# LED_Matrix.net
KiCad netlist of a schematic drawn in Altium Designer
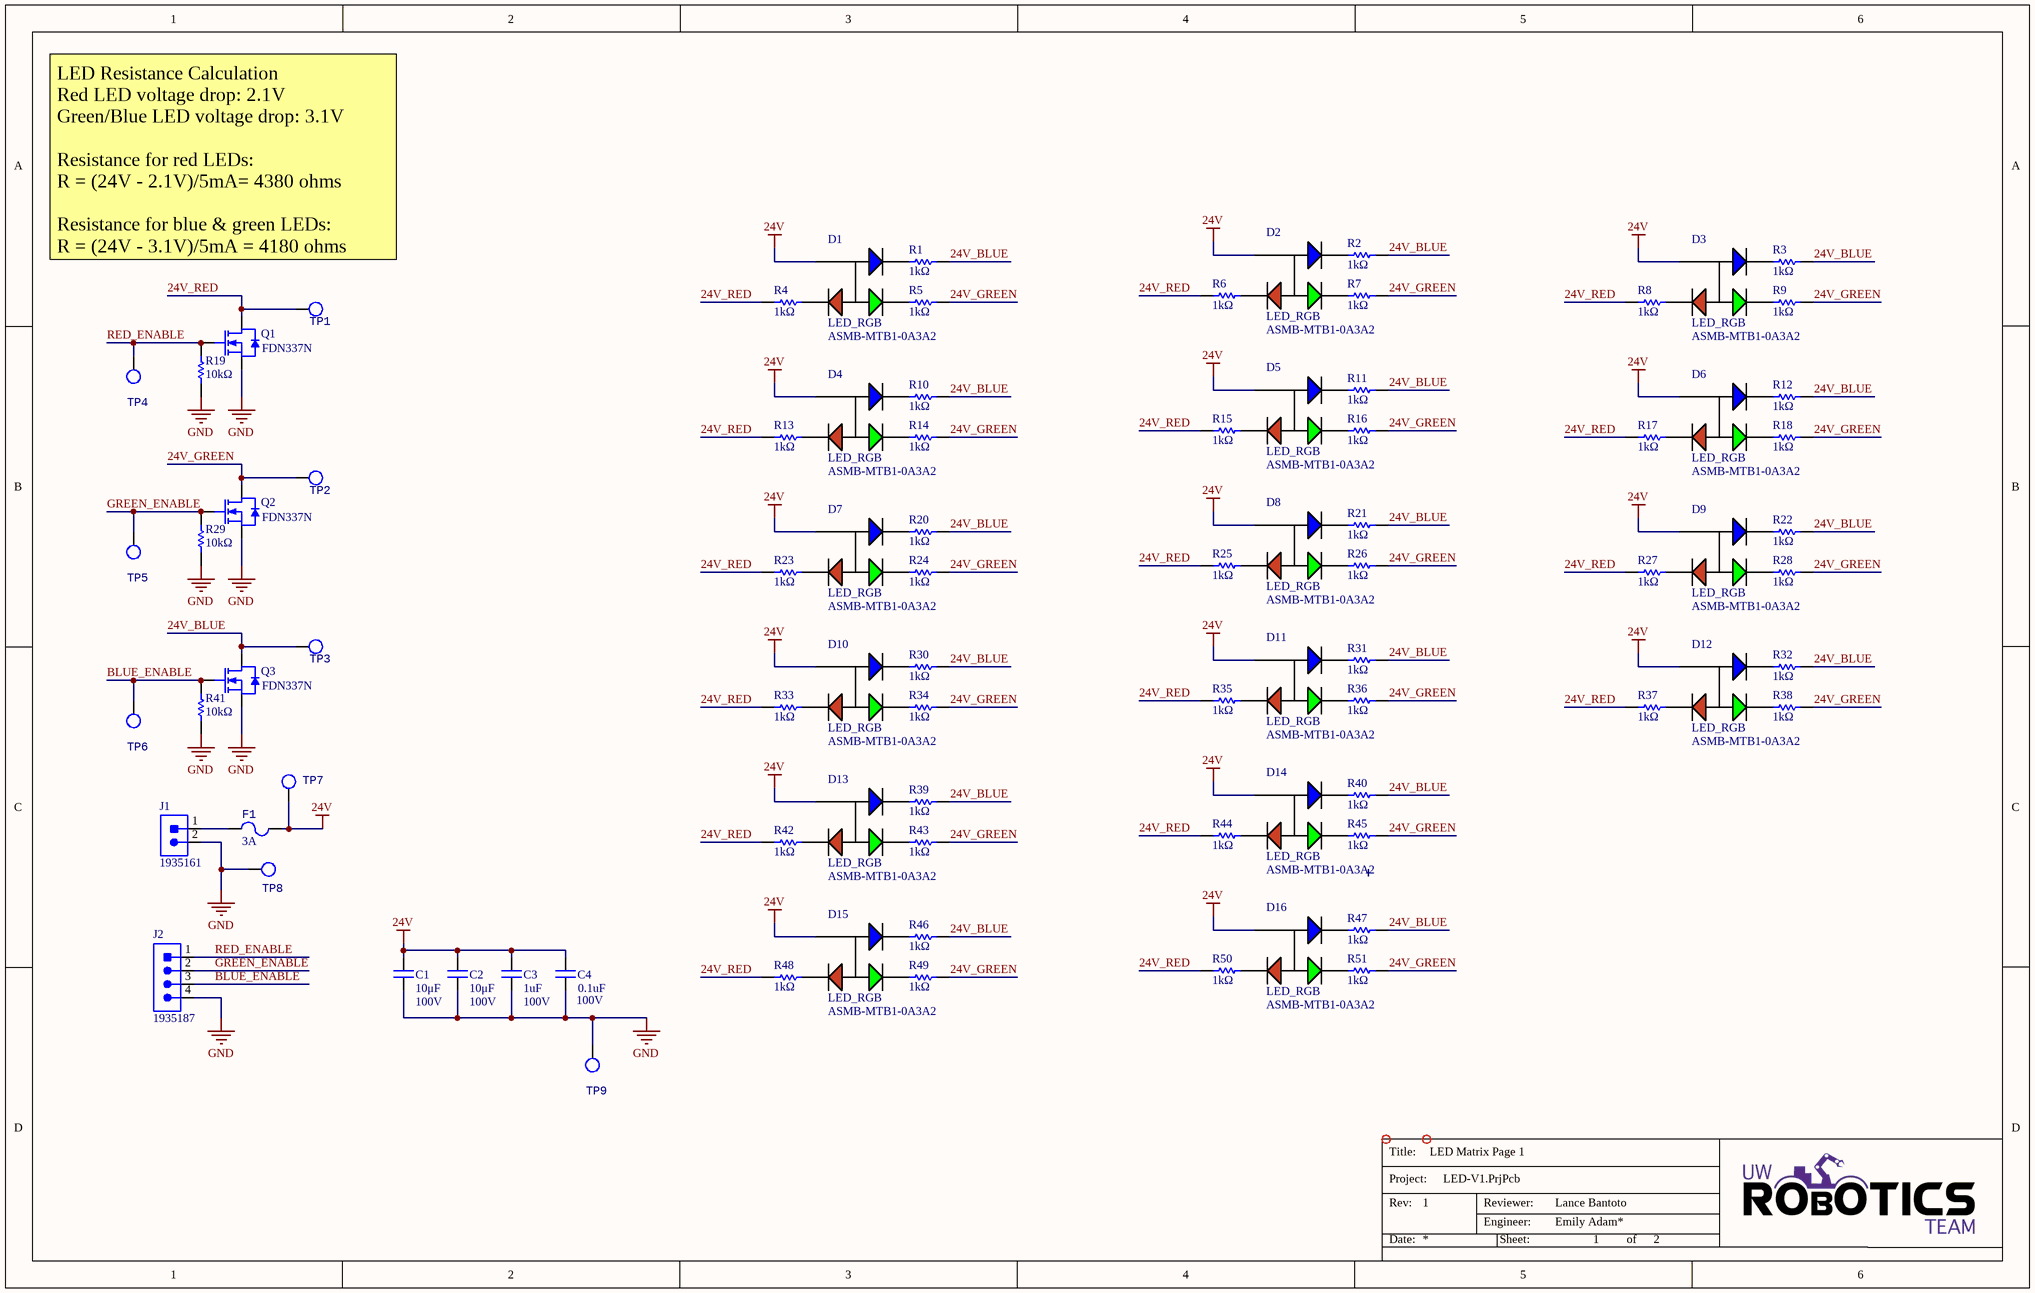
[diagram p0: LED Matrix.SchDoc]

(export (version "E")
  (design (tool "Eeschema 10.0.6"))
  (components
    (comp (ref "C1")
      (value "10μF")
      (footprint "CAP1210")
      (description "CAP CER 10uF 100V X7S 10% 1210")
      (fields
        (field (name "TOLERANCE") "10%")
        (field (name "VOLTAGE RATING") "100V")
        (field (name "Comment") "CAP_10uF_100V_1210")
      )
      (libsource (lib "UWRT_Schematic_Library_2020") (part "CAP_10uF_100V_1210"))
    )
    (comp (ref "C2")
      (value "10μF")
      (footprint "CAP1210")
      (description "CAP CER 10uF 100V X7S 10% 1210")
      (fields
        (field (name "TOLERANCE") "10%")
        (field (name "VOLTAGE RATING") "100V")
        (field (name "Comment") "CAP_10uF_100V_1210")
      )
      (libsource (lib "UWRT_Schematic_Library_2020") (part "CAP_10uF_100V_1210"))
    )
    (comp (ref "C3")
      (value "CAP_1uF_100V_1206")
      (footprint "CAPC3216X190X50NL20T25")
      (description "CAP CER 1UF 100V X7R 1206")
      (fields
        (field (name "MANUFACTURER") "Murata")
        (field (name "MANUFACTURER PART NUMBER") "GCJ31CR72A105KA01L")
        (field (name "CAPACITANCE") "1uF")
        (field (name "VOLTAGE RATING") "100V")
      )
      (libsource (lib "UWRT_Schematic_Library_2020") (part "CAP_1uF_100V_1206"))
    )
    (comp (ref "C4")
      (value "CAP_0.1uF_100V_1206")
      (footprint "CAPC3216X180N")
      (description "CAP CER 0.1UF 100V C0G/NP0 1206")
      (fields
        (field (name "MANUFACTURER") "Murata")
        (field (name "MANUFACTURER PART NUMBER") "GRM31C5C2A104JA01L")
        (field (name "VOLTAGE RATING (DC)") "100V")
        (field (name "CAPACITANCE") "0.1uF")
      )
      (libsource (lib "UWRT_Schematic_Library_2020") (part "CAP_0.1uF_100V_1206"))
    )
    (comp (ref "D1")
      (value "LED_RGB")
      (footprint "LED_RGB")
      (description "LED RGB DIFFUSED 4PLCC SMD")
      (fields (field (name "MANUFACTURER PART NUMBER 1") "ASMB-MTB1-0A3A2"))
      (libsource (lib "UWRT_Schematic_Library_2020") (part "LED_RGB"))
    )
    (comp (ref "D2")
      (value "LED_RGB")
      (footprint "LED_RGB")
      (description "LED RGB DIFFUSED 4PLCC SMD")
      (fields (field (name "MANUFACTURER PART NUMBER 1") "ASMB-MTB1-0A3A2"))
      (libsource (lib "UWRT_Schematic_Library_2020") (part "LED_RGB"))
    )
    (comp (ref "D3")
      (value "LED_RGB")
      (footprint "LED_RGB")
      (description "LED RGB DIFFUSED 4PLCC SMD")
      (fields (field (name "MANUFACTURER PART NUMBER 1") "ASMB-MTB1-0A3A2"))
      (libsource (lib "UWRT_Schematic_Library_2020") (part "LED_RGB"))
    )
    (comp (ref "D4")
      (value "LED_RGB")
      (footprint "LED_RGB")
      (description "LED RGB DIFFUSED 4PLCC SMD")
      (fields (field (name "MANUFACTURER PART NUMBER 1") "ASMB-MTB1-0A3A2"))
      (libsource (lib "UWRT_Schematic_Library_2020") (part "LED_RGB"))
    )
    (comp (ref "D5")
      (value "LED_RGB")
      (footprint "LED_RGB")
      (description "LED RGB DIFFUSED 4PLCC SMD")
      (fields (field (name "MANUFACTURER PART NUMBER 1") "ASMB-MTB1-0A3A2"))
      (libsource (lib "UWRT_Schematic_Library_2020") (part "LED_RGB"))
    )
    (comp (ref "D6")
      (value "LED_RGB")
      (footprint "LED_RGB")
      (description "LED RGB DIFFUSED 4PLCC SMD")
      (fields (field (name "MANUFACTURER PART NUMBER 1") "ASMB-MTB1-0A3A2"))
      (libsource (lib "UWRT_Schematic_Library_2020") (part "LED_RGB"))
    )
    (comp (ref "D7")
      (value "LED_RGB")
      (footprint "LED_RGB")
      (description "LED RGB DIFFUSED 4PLCC SMD")
      (fields (field (name "MANUFACTURER PART NUMBER 1") "ASMB-MTB1-0A3A2"))
      (libsource (lib "UWRT_Schematic_Library_2020") (part "LED_RGB"))
    )
    (comp (ref "D8")
      (value "LED_RGB")
      (footprint "LED_RGB")
      (description "LED RGB DIFFUSED 4PLCC SMD")
      (fields (field (name "MANUFACTURER PART NUMBER 1") "ASMB-MTB1-0A3A2"))
      (libsource (lib "UWRT_Schematic_Library_2020") (part "LED_RGB"))
    )
    (comp (ref "D9")
      (value "LED_RGB")
      (footprint "LED_RGB")
      (description "LED RGB DIFFUSED 4PLCC SMD")
      (fields (field (name "MANUFACTURER PART NUMBER 1") "ASMB-MTB1-0A3A2"))
      (libsource (lib "UWRT_Schematic_Library_2020") (part "LED_RGB"))
    )
    (comp (ref "D10")
      (value "LED_RGB")
      (footprint "LED_RGB")
      (description "LED RGB DIFFUSED 4PLCC SMD")
      (fields (field (name "MANUFACTURER PART NUMBER 1") "ASMB-MTB1-0A3A2"))
      (libsource (lib "UWRT_Schematic_Library_2020") (part "LED_RGB"))
    )
    (comp (ref "D11")
      (value "LED_RGB")
      (footprint "LED_RGB")
      (description "LED RGB DIFFUSED 4PLCC SMD")
      (fields (field (name "MANUFACTURER PART NUMBER 1") "ASMB-MTB1-0A3A2"))
      (libsource (lib "UWRT_Schematic_Library_2020") (part "LED_RGB"))
    )
    (comp (ref "D12")
      (value "LED_RGB")
      (footprint "LED_RGB")
      (description "LED RGB DIFFUSED 4PLCC SMD")
      (fields (field (name "MANUFACTURER PART NUMBER 1") "ASMB-MTB1-0A3A2"))
      (libsource (lib "UWRT_Schematic_Library_2020") (part "LED_RGB"))
    )
    (comp (ref "D13")
      (value "LED_RGB")
      (footprint "LED_RGB")
      (description "LED RGB DIFFUSED 4PLCC SMD")
      (fields (field (name "MANUFACTURER PART NUMBER 1") "ASMB-MTB1-0A3A2"))
      (libsource (lib "UWRT_Schematic_Library_2020") (part "LED_RGB"))
    )
    (comp (ref "D14")
      (value "LED_RGB")
      (footprint "LED_RGB")
      (description "LED RGB DIFFUSED 4PLCC SMD")
      (fields (field (name "MANUFACTURER PART NUMBER 1") "ASMB-MTB1-0A3A2"))
      (libsource (lib "UWRT_Schematic_Library_2020") (part "LED_RGB"))
    )
    (comp (ref "D15")
      (value "LED_RGB")
      (footprint "LED_RGB")
      (description "LED RGB DIFFUSED 4PLCC SMD")
      (fields (field (name "MANUFACTURER PART NUMBER 1") "ASMB-MTB1-0A3A2"))
      (libsource (lib "UWRT_Schematic_Library_2020") (part "LED_RGB"))
    )
    (comp (ref "D16")
      (value "LED_RGB")
      (footprint "LED_RGB")
      (description "LED RGB DIFFUSED 4PLCC SMD")
      (fields (field (name "MANUFACTURER PART NUMBER 1") "ASMB-MTB1-0A3A2"))
      (libsource (lib "UWRT_Schematic_Library_2020") (part "LED_RGB"))
    )
    (comp (ref "F1")
      (value "FUSE_3A_1206")
      (footprint "FUSE_1206")
      (description "FUSE BOARD MNT 3A 32VAC/VDC 1206")
      (fields (field (name "CURRENT RATING") "3A"))
      (libsource (lib "UWRT_Schematic_Library_2020") (part "FUSE_3A_1206"))
    )
    (comp (ref "J1")
      (value "CON_2M_TERM")
      (footprint "1935161")
      (description "TERM BLK 2POS SIDE ENTRY 5MM")
      (fields (field (name "VOLTAGE") "300V") (field (name "MANUFACTURER PART NUMBER 1") "1935161"))
      (libsource (lib "UWRT_Schematic_Library_2020") (part "CON_2M_TERM"))
    )
    (comp (ref "J2")
      (value "CON_4M_TERM")
      (footprint "1935187")
      (description "TERM BLK 4POS SIDE ENTRY 5MM PCB")
      (fields (field (name "VOLTAGE") "300V") (field (name "MANUFACTURER PART NUMBER 1") "1935187"))
      (libsource (lib "UWRT_Schematic_Library_2020") (part "CON_4M_TERM"))
    )
    (comp (ref "MH1")
      (value "MOUNTING_HOLES")
      (footprint "MOUNTING_HOLE")
      (description "6cm x 6cm")
      (libsource (lib "UWRT_Schematic_Library_2020") (part "MOUNTING_HOLES"))
    )
    (comp (ref "MH2")
      (value "MOUNTING_HOLES")
      (footprint "MOUNTING_HOLE")
      (description "6cm x 6cm")
      (libsource (lib "UWRT_Schematic_Library_2020") (part "MOUNTING_HOLES"))
    )
    (comp (ref "Q1")
      (value "NMOS_30V_2.2A")
      (footprint "NMOS_SSOT-3")
      (description "MOSFET N-CH 30V 2.2A SUPERSOT3")
      (fields (field (name "MANUFACTURER PART NUMBER 1") "FDN337N"))
      (libsource (lib "UWRT_Schematic_Library_2020") (part "NMOS_30V_2.2A"))
    )
    (comp (ref "Q2")
      (value "NMOS_30V_2.2A")
      (footprint "NMOS_SSOT-3")
      (description "MOSFET N-CH 30V 2.2A SUPERSOT3")
      (fields (field (name "MANUFACTURER PART NUMBER 1") "FDN337N"))
      (libsource (lib "UWRT_Schematic_Library_2020") (part "NMOS_30V_2.2A"))
    )
    (comp (ref "Q3")
      (value "NMOS_30V_2.2A")
      (footprint "NMOS_SSOT-3")
      (description "MOSFET N-CH 30V 2.2A SUPERSOT3")
      (fields (field (name "MANUFACTURER PART NUMBER 1") "FDN337N"))
      (libsource (lib "UWRT_Schematic_Library_2020") (part "NMOS_30V_2.2A"))
    )
    (comp (ref "R1")
      (value "1kΩ")
      (footprint "RESC2012X60N")
      (description "RES SMD 1K OHM 1% 1/8W 0805")
      (fields (field (name "TOLERANCE") "1%"))
      (libsource (lib "UWRT_Schematic_Library_2020") (part "RES_1kΩ_0805"))
    )
    (comp (ref "R2")
      (value "1kΩ")
      (footprint "RESC2012X60N")
      (description "RES SMD 1K OHM 1% 1/8W 0805")
      (fields (field (name "TOLERANCE") "1%"))
      (libsource (lib "UWRT_Schematic_Library_2020") (part "RES_1kΩ_0805"))
    )
    (comp (ref "R3")
      (value "1kΩ")
      (footprint "RESC2012X60N")
      (description "RES SMD 1K OHM 1% 1/8W 0805")
      (fields (field (name "TOLERANCE") "1%"))
      (libsource (lib "UWRT_Schematic_Library_2020") (part "RES_1kΩ_0805"))
    )
    (comp (ref "R4")
      (value "1kΩ")
      (footprint "RESC2012X60N")
      (description "RES SMD 1K OHM 1% 1/8W 0805")
      (fields (field (name "TOLERANCE") "1%"))
      (libsource (lib "UWRT_Schematic_Library_2020") (part "RES_1kΩ_0805"))
    )
    (comp (ref "R5")
      (value "1kΩ")
      (footprint "RESC2012X60N")
      (description "RES SMD 1K OHM 1% 1/8W 0805")
      (fields (field (name "TOLERANCE") "1%"))
      (libsource (lib "UWRT_Schematic_Library_2020") (part "RES_1kΩ_0805"))
    )
    (comp (ref "R6")
      (value "1kΩ")
      (footprint "RESC2012X60N")
      (description "RES SMD 1K OHM 1% 1/8W 0805")
      (fields (field (name "TOLERANCE") "1%"))
      (libsource (lib "UWRT_Schematic_Library_2020") (part "RES_1kΩ_0805"))
    )
    (comp (ref "R7")
      (value "1kΩ")
      (footprint "RESC2012X60N")
      (description "RES SMD 1K OHM 1% 1/8W 0805")
      (fields (field (name "TOLERANCE") "1%"))
      (libsource (lib "UWRT_Schematic_Library_2020") (part "RES_1kΩ_0805"))
    )
    (comp (ref "R8")
      (value "1kΩ")
      (footprint "RESC2012X60N")
      (description "RES SMD 1K OHM 1% 1/8W 0805")
      (fields (field (name "TOLERANCE") "1%"))
      (libsource (lib "UWRT_Schematic_Library_2020") (part "RES_1kΩ_0805"))
    )
    (comp (ref "R9")
      (value "1kΩ")
      (footprint "RESC2012X60N")
      (description "RES SMD 1K OHM 1% 1/8W 0805")
      (fields (field (name "TOLERANCE") "1%"))
      (libsource (lib "UWRT_Schematic_Library_2020") (part "RES_1kΩ_0805"))
    )
    (comp (ref "R10")
      (value "1kΩ")
      (footprint "RESC2012X60N")
      (description "RES SMD 1K OHM 1% 1/8W 0805")
      (fields (field (name "TOLERANCE") "1%"))
      (libsource (lib "UWRT_Schematic_Library_2020") (part "RES_1kΩ_0805"))
    )
    (comp (ref "R11")
      (value "1kΩ")
      (footprint "RESC2012X60N")
      (description "RES SMD 1K OHM 1% 1/8W 0805")
      (fields (field (name "TOLERANCE") "1%"))
      (libsource (lib "UWRT_Schematic_Library_2020") (part "RES_1kΩ_0805"))
    )
    (comp (ref "R12")
      (value "1kΩ")
      (footprint "RESC2012X60N")
      (description "RES SMD 1K OHM 1% 1/8W 0805")
      (fields (field (name "TOLERANCE") "1%"))
      (libsource (lib "UWRT_Schematic_Library_2020") (part "RES_1kΩ_0805"))
    )
    (comp (ref "R13")
      (value "1kΩ")
      (footprint "RESC2012X60N")
      (description "RES SMD 1K OHM 1% 1/8W 0805")
      (fields (field (name "TOLERANCE") "1%"))
      (libsource (lib "UWRT_Schematic_Library_2020") (part "RES_1kΩ_0805"))
    )
    (comp (ref "R14")
      (value "1kΩ")
      (footprint "RESC2012X60N")
      (description "RES SMD 1K OHM 1% 1/8W 0805")
      (fields (field (name "TOLERANCE") "1%"))
      (libsource (lib "UWRT_Schematic_Library_2020") (part "RES_1kΩ_0805"))
    )
    (comp (ref "R15")
      (value "1kΩ")
      (footprint "RESC2012X60N")
      (description "RES SMD 1K OHM 1% 1/8W 0805")
      (fields (field (name "TOLERANCE") "1%"))
      (libsource (lib "UWRT_Schematic_Library_2020") (part "RES_1kΩ_0805"))
    )
    (comp (ref "R16")
      (value "1kΩ")
      (footprint "RESC2012X60N")
      (description "RES SMD 1K OHM 1% 1/8W 0805")
      (fields (field (name "TOLERANCE") "1%"))
      (libsource (lib "UWRT_Schematic_Library_2020") (part "RES_1kΩ_0805"))
    )
    (comp (ref "R17")
      (value "1kΩ")
      (footprint "RESC2012X60N")
      (description "RES SMD 1K OHM 1% 1/8W 0805")
      (fields (field (name "TOLERANCE") "1%"))
      (libsource (lib "UWRT_Schematic_Library_2020") (part "RES_1kΩ_0805"))
    )
    (comp (ref "R18")
      (value "1kΩ")
      (footprint "RESC2012X60N")
      (description "RES SMD 1K OHM 1% 1/8W 0805")
      (fields (field (name "TOLERANCE") "1%"))
      (libsource (lib "UWRT_Schematic_Library_2020") (part "RES_1kΩ_0805"))
    )
    (comp (ref "R19")
      (value "10kΩ")
      (footprint "RESC2012X60N")
      (description "RES SMD 10K OHM 1% 1/8W 0805")
      (fields (field (name "TOLERANCE") "1%") (field (name "Comment") "RES_10kΩ_0805"))
      (libsource (lib "UWRT_Schematic_Library_2020") (part "RES_10kΩ_0805"))
    )
    (comp (ref "R20")
      (value "1kΩ")
      (footprint "RESC2012X60N")
      (description "RES SMD 1K OHM 1% 1/8W 0805")
      (fields (field (name "TOLERANCE") "1%"))
      (libsource (lib "UWRT_Schematic_Library_2020") (part "RES_1kΩ_0805"))
    )
    (comp (ref "R21")
      (value "1kΩ")
      (footprint "RESC2012X60N")
      (description "RES SMD 1K OHM 1% 1/8W 0805")
      (fields (field (name "TOLERANCE") "1%"))
      (libsource (lib "UWRT_Schematic_Library_2020") (part "RES_1kΩ_0805"))
    )
    (comp (ref "R22")
      (value "1kΩ")
      (footprint "RESC2012X60N")
      (description "RES SMD 1K OHM 1% 1/8W 0805")
      (fields (field (name "TOLERANCE") "1%"))
      (libsource (lib "UWRT_Schematic_Library_2020") (part "RES_1kΩ_0805"))
    )
    (comp (ref "R23")
      (value "1kΩ")
      (footprint "RESC2012X60N")
      (description "RES SMD 1K OHM 1% 1/8W 0805")
      (fields (field (name "TOLERANCE") "1%"))
      (libsource (lib "UWRT_Schematic_Library_2020") (part "RES_1kΩ_0805"))
    )
    (comp (ref "R24")
      (value "1kΩ")
      (footprint "RESC2012X60N")
      (description "RES SMD 1K OHM 1% 1/8W 0805")
      (fields (field (name "TOLERANCE") "1%"))
      (libsource (lib "UWRT_Schematic_Library_2020") (part "RES_1kΩ_0805"))
    )
    (comp (ref "R25")
      (value "1kΩ")
      (footprint "RESC2012X60N")
      (description "RES SMD 1K OHM 1% 1/8W 0805")
      (fields (field (name "TOLERANCE") "1%"))
      (libsource (lib "UWRT_Schematic_Library_2020") (part "RES_1kΩ_0805"))
    )
    (comp (ref "R26")
      (value "1kΩ")
      (footprint "RESC2012X60N")
      (description "RES SMD 1K OHM 1% 1/8W 0805")
      (fields (field (name "TOLERANCE") "1%"))
      (libsource (lib "UWRT_Schematic_Library_2020") (part "RES_1kΩ_0805"))
    )
    (comp (ref "R27")
      (value "1kΩ")
      (footprint "RESC2012X60N")
      (description "RES SMD 1K OHM 1% 1/8W 0805")
      (fields (field (name "TOLERANCE") "1%"))
      (libsource (lib "UWRT_Schematic_Library_2020") (part "RES_1kΩ_0805"))
    )
    (comp (ref "R28")
      (value "1kΩ")
      (footprint "RESC2012X60N")
      (description "RES SMD 1K OHM 1% 1/8W 0805")
      (fields (field (name "TOLERANCE") "1%"))
      (libsource (lib "UWRT_Schematic_Library_2020") (part "RES_1kΩ_0805"))
    )
    (comp (ref "R29")
      (value "10kΩ")
      (footprint "RESC2012X60N")
      (description "RES SMD 10K OHM 1% 1/8W 0805")
      (fields (field (name "TOLERANCE") "1%") (field (name "Comment") "RES_10kΩ_0805"))
      (libsource (lib "UWRT_Schematic_Library_2020") (part "RES_10kΩ_0805"))
    )
    (comp (ref "R30")
      (value "1kΩ")
      (footprint "RESC2012X60N")
      (description "RES SMD 1K OHM 1% 1/8W 0805")
      (fields (field (name "TOLERANCE") "1%"))
      (libsource (lib "UWRT_Schematic_Library_2020") (part "RES_1kΩ_0805"))
    )
    (comp (ref "R31")
      (value "1kΩ")
      (footprint "RESC2012X60N")
      (description "RES SMD 1K OHM 1% 1/8W 0805")
      (fields (field (name "TOLERANCE") "1%"))
      (libsource (lib "UWRT_Schematic_Library_2020") (part "RES_1kΩ_0805"))
    )
    (comp (ref "R32")
      (value "1kΩ")
      (footprint "RESC2012X60N")
      (description "RES SMD 1K OHM 1% 1/8W 0805")
      (fields (field (name "TOLERANCE") "1%"))
      (libsource (lib "UWRT_Schematic_Library_2020") (part "RES_1kΩ_0805"))
    )
    (comp (ref "R33")
      (value "1kΩ")
      (footprint "RESC2012X60N")
      (description "RES SMD 1K OHM 1% 1/8W 0805")
      (fields (field (name "TOLERANCE") "1%"))
      (libsource (lib "UWRT_Schematic_Library_2020") (part "RES_1kΩ_0805"))
    )
    (comp (ref "R34")
      (value "1kΩ")
      (footprint "RESC2012X60N")
      (description "RES SMD 1K OHM 1% 1/8W 0805")
      (fields (field (name "TOLERANCE") "1%"))
      (libsource (lib "UWRT_Schematic_Library_2020") (part "RES_1kΩ_0805"))
    )
    (comp (ref "R35")
      (value "1kΩ")
      (footprint "RESC2012X60N")
      (description "RES SMD 1K OHM 1% 1/8W 0805")
      (fields (field (name "TOLERANCE") "1%"))
      (libsource (lib "UWRT_Schematic_Library_2020") (part "RES_1kΩ_0805"))
    )
    (comp (ref "R36")
      (value "1kΩ")
      (footprint "RESC2012X60N")
      (description "RES SMD 1K OHM 1% 1/8W 0805")
      (fields (field (name "TOLERANCE") "1%"))
      (libsource (lib "UWRT_Schematic_Library_2020") (part "RES_1kΩ_0805"))
    )
    (comp (ref "R37")
      (value "1kΩ")
      (footprint "RESC2012X60N")
      (description "RES SMD 1K OHM 1% 1/8W 0805")
      (fields (field (name "TOLERANCE") "1%"))
      (libsource (lib "UWRT_Schematic_Library_2020") (part "RES_1kΩ_0805"))
    )
    (comp (ref "R38")
      (value "1kΩ")
      (footprint "RESC2012X60N")
      (description "RES SMD 1K OHM 1% 1/8W 0805")
      (fields (field (name "TOLERANCE") "1%"))
      (libsource (lib "UWRT_Schematic_Library_2020") (part "RES_1kΩ_0805"))
    )
    (comp (ref "R39")
      (value "1kΩ")
      (footprint "RESC2012X60N")
      (description "RES SMD 1K OHM 1% 1/8W 0805")
      (fields (field (name "TOLERANCE") "1%"))
      (libsource (lib "UWRT_Schematic_Library_2020") (part "RES_1kΩ_0805"))
    )
    (comp (ref "R40")
      (value "1kΩ")
      (footprint "RESC2012X60N")
      (description "RES SMD 1K OHM 1% 1/8W 0805")
      (fields (field (name "TOLERANCE") "1%"))
      (libsource (lib "UWRT_Schematic_Library_2020") (part "RES_1kΩ_0805"))
    )
    (comp (ref "R41")
      (value "10kΩ")
      (footprint "RESC2012X60N")
      (description "RES SMD 10K OHM 1% 1/8W 0805")
      (fields (field (name "TOLERANCE") "1%") (field (name "Comment") "RES_10kΩ_0805"))
      (libsource (lib "UWRT_Schematic_Library_2020") (part "RES_10kΩ_0805"))
    )
    (comp (ref "R42")
      (value "1kΩ")
      (footprint "RESC2012X60N")
      (description "RES SMD 1K OHM 1% 1/8W 0805")
      (fields (field (name "TOLERANCE") "1%"))
      (libsource (lib "UWRT_Schematic_Library_2020") (part "RES_1kΩ_0805"))
    )
    (comp (ref "R43")
      (value "1kΩ")
      (footprint "RESC2012X60N")
      (description "RES SMD 1K OHM 1% 1/8W 0805")
      (fields (field (name "TOLERANCE") "1%"))
      (libsource (lib "UWRT_Schematic_Library_2020") (part "RES_1kΩ_0805"))
    )
    (comp (ref "R44")
      (value "1kΩ")
      (footprint "RESC2012X60N")
      (description "RES SMD 1K OHM 1% 1/8W 0805")
      (fields (field (name "TOLERANCE") "1%"))
      (libsource (lib "UWRT_Schematic_Library_2020") (part "RES_1kΩ_0805"))
    )
    (comp (ref "R45")
      (value "1kΩ")
      (footprint "RESC2012X60N")
      (description "RES SMD 1K OHM 1% 1/8W 0805")
      (fields (field (name "TOLERANCE") "1%"))
      (libsource (lib "UWRT_Schematic_Library_2020") (part "RES_1kΩ_0805"))
    )
    (comp (ref "R46")
      (value "1kΩ")
      (footprint "RESC2012X60N")
      (description "RES SMD 1K OHM 1% 1/8W 0805")
      (fields (field (name "TOLERANCE") "1%"))
      (libsource (lib "UWRT_Schematic_Library_2020") (part "RES_1kΩ_0805"))
    )
    (comp (ref "R47")
      (value "1kΩ")
      (footprint "RESC2012X60N")
      (description "RES SMD 1K OHM 1% 1/8W 0805")
      (fields (field (name "TOLERANCE") "1%"))
      (libsource (lib "UWRT_Schematic_Library_2020") (part "RES_1kΩ_0805"))
    )
    (comp (ref "R48")
      (value "1kΩ")
      (footprint "RESC2012X60N")
      (description "RES SMD 1K OHM 1% 1/8W 0805")
      (fields (field (name "TOLERANCE") "1%"))
      (libsource (lib "UWRT_Schematic_Library_2020") (part "RES_1kΩ_0805"))
    )
    (comp (ref "R49")
      (value "1kΩ")
      (footprint "RESC2012X60N")
      (description "RES SMD 1K OHM 1% 1/8W 0805")
      (fields (field (name "TOLERANCE") "1%"))
      (libsource (lib "UWRT_Schematic_Library_2020") (part "RES_1kΩ_0805"))
    )
    (comp (ref "R50")
      (value "1kΩ")
      (footprint "RESC2012X60N")
      (description "RES SMD 1K OHM 1% 1/8W 0805")
      (fields (field (name "TOLERANCE") "1%"))
      (libsource (lib "UWRT_Schematic_Library_2020") (part "RES_1kΩ_0805"))
    )
    (comp (ref "R51")
      (value "1kΩ")
      (footprint "RESC2012X60N")
      (description "RES SMD 1K OHM 1% 1/8W 0805")
      (fields (field (name "TOLERANCE") "1%"))
      (libsource (lib "UWRT_Schematic_Library_2020") (part "RES_1kΩ_0805"))
    )
    (comp (ref "TP1")
      (value "TESTPOINT_LOOP")
      (footprint "TESTPOINT_LOOP")
      (description "PC TEST POINT MINIATURE WHITE")
      (libsource (lib "UWRT_Schematic_Library_2020") (part "TESTPOINT_LOOP"))
    )
    (comp (ref "TP2")
      (value "TESTPOINT_LOOP")
      (footprint "TESTPOINT_LOOP")
      (description "PC TEST POINT MINIATURE WHITE")
      (libsource (lib "UWRT_Schematic_Library_2020") (part "TESTPOINT_LOOP"))
    )
    (comp (ref "TP3")
      (value "TESTPOINT_LOOP")
      (footprint "TESTPOINT_LOOP")
      (description "PC TEST POINT MINIATURE WHITE")
      (libsource (lib "UWRT_Schematic_Library_2020") (part "TESTPOINT_LOOP"))
    )
    (comp (ref "TP4")
      (value "TESTPOINT_LOOP")
      (footprint "TESTPOINT_LOOP")
      (description "PC TEST POINT MINIATURE WHITE")
      (libsource (lib "UWRT_Schematic_Library_2020") (part "TESTPOINT_LOOP"))
    )
    (comp (ref "TP5")
      (value "TESTPOINT_LOOP")
      (footprint "TESTPOINT_LOOP")
      (description "PC TEST POINT MINIATURE WHITE")
      (libsource (lib "UWRT_Schematic_Library_2020") (part "TESTPOINT_LOOP"))
    )
    (comp (ref "TP6")
      (value "TESTPOINT_LOOP")
      (footprint "TESTPOINT_LOOP")
      (description "PC TEST POINT MINIATURE WHITE")
      (libsource (lib "UWRT_Schematic_Library_2020") (part "TESTPOINT_LOOP"))
    )
    (comp (ref "TP7")
      (value "TESTPOINT_LOOP")
      (footprint "TESTPOINT_LOOP")
      (description "PC TEST POINT MINIATURE WHITE")
      (libsource (lib "UWRT_Schematic_Library_2020") (part "TESTPOINT_LOOP"))
    )
    (comp (ref "TP8")
      (value "TESTPOINT_LOOP")
      (footprint "TESTPOINT_LOOP")
      (description "PC TEST POINT MINIATURE WHITE")
      (libsource (lib "UWRT_Schematic_Library_2020") (part "TESTPOINT_LOOP"))
    )
    (comp (ref "TP9")
      (value "TESTPOINT_LOOP")
      (footprint "TESTPOINT_LOOP")
      (description "PC TEST POINT MINIATURE WHITE")
      (libsource (lib "UWRT_Schematic_Library_2020") (part "TESTPOINT_LOOP"))
    )
  )
  (nets
    (net (code "1") (name "/24V_BLUE") (class "Default")
      (node (ref "Q3") (pin "3") (pinfunction "DRAIN_3") (pintype "passive"))
      (node (ref "R1") (pin "2") (pinfunction "2_2") (pintype "passive"))
      (node (ref "R10") (pin "2") (pinfunction "2_2") (pintype "passive"))
      (node (ref "R11") (pin "2") (pinfunction "2_2") (pintype "passive"))
      (node (ref "R12") (pin "2") (pinfunction "2_2") (pintype "passive"))
      (node (ref "R2") (pin "2") (pinfunction "2_2") (pintype "passive"))
      (node (ref "R20") (pin "1") (pinfunction "1_1") (pintype "passive"))
      (node (ref "R21") (pin "1") (pinfunction "1_1") (pintype "passive"))
      (node (ref "R22") (pin "1") (pinfunction "1_1") (pintype "passive"))
      (node (ref "R3") (pin "2") (pinfunction "2_2") (pintype "passive"))
      (node (ref "R30") (pin "2") (pinfunction "2_2") (pintype "passive"))
      (node (ref "R31") (pin "2") (pinfunction "2_2") (pintype "passive"))
      (node (ref "R32") (pin "2") (pinfunction "2_2") (pintype "passive"))
      (node (ref "R39") (pin "1") (pinfunction "1_1") (pintype "passive"))
      (node (ref "R40") (pin "2") (pinfunction "2_2") (pintype "passive"))
      (node (ref "R46") (pin "2") (pinfunction "2_2") (pintype "passive"))
      (node (ref "R47") (pin "2") (pinfunction "2_2") (pintype "passive"))
      (node (ref "TP3") (pin "1") (pintype "passive"))
    )
    (net (code "2") (name "/24V_GREEN") (class "Default")
      (node (ref "Q2") (pin "3") (pinfunction "DRAIN_3") (pintype "passive"))
      (node (ref "R14") (pin "2") (pinfunction "2_2") (pintype "passive"))
      (node (ref "R16") (pin "2") (pinfunction "2_2") (pintype "passive"))
      (node (ref "R18") (pin "2") (pinfunction "2_2") (pintype "passive"))
      (node (ref "R24") (pin "2") (pinfunction "2_2") (pintype "passive"))
      (node (ref "R26") (pin "2") (pinfunction "2_2") (pintype "passive"))
      (node (ref "R28") (pin "2") (pinfunction "2_2") (pintype "passive"))
      (node (ref "R34") (pin "2") (pinfunction "2_2") (pintype "passive"))
      (node (ref "R36") (pin "2") (pinfunction "2_2") (pintype "passive"))
      (node (ref "R38") (pin "2") (pinfunction "2_2") (pintype "passive"))
      (node (ref "R43") (pin "2") (pinfunction "2_2") (pintype "passive"))
      (node (ref "R45") (pin "2") (pinfunction "2_2") (pintype "passive"))
      (node (ref "R49") (pin "2") (pinfunction "2_2") (pintype "passive"))
      (node (ref "R5") (pin "2") (pinfunction "2_2") (pintype "passive"))
      (node (ref "R51") (pin "2") (pinfunction "2_2") (pintype "passive"))
      (node (ref "R7") (pin "2") (pinfunction "2_2") (pintype "passive"))
      (node (ref "R9") (pin "2") (pinfunction "2_2") (pintype "passive"))
      (node (ref "TP2") (pin "1") (pintype "passive"))
    )
    (net (code "3") (name "/24V_RED") (class "Default")
      (node (ref "Q1") (pin "3") (pinfunction "DRAIN_3") (pintype "passive"))
      (node (ref "R13") (pin "1") (pinfunction "1_1") (pintype "passive"))
      (node (ref "R15") (pin "1") (pinfunction "1_1") (pintype "passive"))
      (node (ref "R17") (pin "1") (pinfunction "1_1") (pintype "passive"))
      (node (ref "R23") (pin "2") (pinfunction "2_2") (pintype "passive"))
      (node (ref "R25") (pin "1") (pinfunction "1_1") (pintype "passive"))
      (node (ref "R27") (pin "1") (pinfunction "1_1") (pintype "passive"))
      (node (ref "R33") (pin "1") (pinfunction "1_1") (pintype "passive"))
      (node (ref "R35") (pin "1") (pinfunction "1_1") (pintype "passive"))
      (node (ref "R37") (pin "1") (pinfunction "1_1") (pintype "passive"))
      (node (ref "R4") (pin "1") (pinfunction "1_1") (pintype "passive"))
      (node (ref "R42") (pin "1") (pinfunction "1_1") (pintype "passive"))
      (node (ref "R44") (pin "1") (pinfunction "1_1") (pintype "passive"))
      (node (ref "R48") (pin "1") (pinfunction "1_1") (pintype "passive"))
      (node (ref "R50") (pin "1") (pinfunction "1_1") (pintype "passive"))
      (node (ref "R6") (pin "1") (pinfunction "1_1") (pintype "passive"))
      (node (ref "R8") (pin "1") (pinfunction "1_1") (pintype "passive"))
      (node (ref "TP1") (pin "1") (pintype "passive"))
    )
    (net (code "4") (name "/BLUE_ENABLE") (class "Default")
      (node (ref "J2") (pin "3") (pinfunction "3_3") (pintype "passive"))
      (node (ref "Q3") (pin "1") (pinfunction "GATE_1") (pintype "passive"))
      (node (ref "R41") (pin "2") (pinfunction "2_2") (pintype "passive"))
      (node (ref "TP6") (pin "1") (pintype "passive"))
    )
    (net (code "5") (name "/GREEN_ENABLE") (class "Default")
      (node (ref "J2") (pin "2") (pinfunction "2_2") (pintype "passive"))
      (node (ref "Q2") (pin "1") (pinfunction "GATE_1") (pintype "passive"))
      (node (ref "R29") (pin "2") (pinfunction "2_2") (pintype "passive"))
      (node (ref "TP5") (pin "1") (pintype "passive"))
    )
    (net (code "6") (name "/RED_ENABLE") (class "Default")
      (node (ref "J2") (pin "1") (pinfunction "1_1") (pintype "passive"))
      (node (ref "Q1") (pin "1") (pinfunction "GATE_1") (pintype "passive"))
      (node (ref "R19") (pin "2") (pinfunction "2_2") (pintype "passive"))
      (node (ref "TP4") (pin "1") (pintype "passive"))
    )
    (net (code "7") (name "24V") (class "Default")
      (node (ref "C1") (pin "2") (pinfunction "2_2") (pintype "passive"))
      (node (ref "C2") (pin "2") (pinfunction "2_2") (pintype "passive"))
      (node (ref "C3") (pin "1") (pinfunction "1_1") (pintype "passive"))
      (node (ref "C4") (pin "2") (pinfunction "2_2") (pintype "passive"))
      (node (ref "D1") (pin "4") (pinfunction "COMMON_ANODE_4") (pintype "passive"))
      (node (ref "D10") (pin "4") (pinfunction "COMMON_ANODE_4") (pintype "passive"))
      (node (ref "D11") (pin "4") (pinfunction "COMMON_ANODE_4") (pintype "passive"))
      (node (ref "D12") (pin "4") (pinfunction "COMMON_ANODE_4") (pintype "passive"))
      (node (ref "D13") (pin "4") (pinfunction "COMMON_ANODE_4") (pintype "passive"))
      (node (ref "D14") (pin "4") (pinfunction "COMMON_ANODE_4") (pintype "passive"))
      (node (ref "D15") (pin "4") (pinfunction "COMMON_ANODE_4") (pintype "passive"))
      (node (ref "D16") (pin "4") (pinfunction "COMMON_ANODE_4") (pintype "passive"))
      (node (ref "D2") (pin "4") (pinfunction "COMMON_ANODE_4") (pintype "passive"))
      (node (ref "D3") (pin "4") (pinfunction "COMMON_ANODE_4") (pintype "passive"))
      (node (ref "D4") (pin "4") (pinfunction "COMMON_ANODE_4") (pintype "passive"))
      (node (ref "D5") (pin "4") (pinfunction "COMMON_ANODE_4") (pintype "passive"))
      (node (ref "D6") (pin "4") (pinfunction "COMMON_ANODE_4") (pintype "passive"))
      (node (ref "D7") (pin "4") (pinfunction "COMMON_ANODE_4") (pintype "passive"))
      (node (ref "D8") (pin "4") (pinfunction "COMMON_ANODE_4") (pintype "passive"))
      (node (ref "D9") (pin "4") (pinfunction "COMMON_ANODE_4") (pintype "passive"))
      (node (ref "F1") (pin "1") (pinfunction "1_1") (pintype "passive"))
      (node (ref "TP7") (pin "1") (pintype "passive"))
    )
    (net (code "8") (name "GND") (class "Default")
      (node (ref "C1") (pin "1") (pinfunction "1_1") (pintype "passive"))
      (node (ref "C2") (pin "1") (pinfunction "1_1") (pintype "passive"))
      (node (ref "C3") (pin "2") (pinfunction "2_2") (pintype "passive"))
      (node (ref "C4") (pin "1") (pinfunction "1_1") (pintype "passive"))
      (node (ref "J1") (pin "2") (pinfunction "2_2") (pintype "passive"))
      (node (ref "J2") (pin "4") (pinfunction "4_4") (pintype "passive"))
      (node (ref "Q1") (pin "2") (pinfunction "SOURCE_2") (pintype "passive"))
      (node (ref "Q2") (pin "2") (pinfunction "SOURCE_2") (pintype "passive"))
      (node (ref "Q3") (pin "2") (pinfunction "SOURCE_2") (pintype "passive"))
      (node (ref "R19") (pin "1") (pinfunction "1_1") (pintype "passive"))
      (node (ref "R29") (pin "1") (pinfunction "1_1") (pintype "passive"))
      (node (ref "R41") (pin "1") (pinfunction "1_1") (pintype "passive"))
      (node (ref "TP8") (pin "1") (pintype "passive"))
      (node (ref "TP9") (pin "1") (pintype "passive"))
    )
    (net (code "9") (name "Net-(D1-CATHODE_(BLUE))") (class "Default")
      (node (ref "D1") (pin "3") (pinfunction "CATHODE_(BLUE)_3") (pintype "passive"))
      (node (ref "R1") (pin "1") (pinfunction "1_1") (pintype "passive"))
    )
    (net (code "10") (name "Net-(D1-CATHODE_(GREEN))") (class "Default")
      (node (ref "D1") (pin "2") (pinfunction "CATHODE_(GREEN)_2") (pintype "passive"))
      (node (ref "R5") (pin "1") (pinfunction "1_1") (pintype "passive"))
    )
    (net (code "11") (name "Net-(D1-CATHODE_(RED))") (class "Default")
      (node (ref "D1") (pin "1") (pinfunction "CATHODE_(RED)_1") (pintype "passive"))
      (node (ref "R4") (pin "2") (pinfunction "2_2") (pintype "passive"))
    )
    (net (code "12") (name "Net-(D2-CATHODE_(BLUE))") (class "Default")
      (node (ref "D2") (pin "3") (pinfunction "CATHODE_(BLUE)_3") (pintype "passive"))
      (node (ref "R2") (pin "1") (pinfunction "1_1") (pintype "passive"))
    )
    (net (code "13") (name "Net-(D2-CATHODE_(GREEN))") (class "Default")
      (node (ref "D2") (pin "2") (pinfunction "CATHODE_(GREEN)_2") (pintype "passive"))
      (node (ref "R7") (pin "1") (pinfunction "1_1") (pintype "passive"))
    )
    (net (code "14") (name "Net-(D2-CATHODE_(RED))") (class "Default")
      (node (ref "D2") (pin "1") (pinfunction "CATHODE_(RED)_1") (pintype "passive"))
      (node (ref "R6") (pin "2") (pinfunction "2_2") (pintype "passive"))
    )
    (net (code "15") (name "Net-(D3-CATHODE_(BLUE))") (class "Default")
      (node (ref "D3") (pin "3") (pinfunction "CATHODE_(BLUE)_3") (pintype "passive"))
      (node (ref "R3") (pin "1") (pinfunction "1_1") (pintype "passive"))
    )
    (net (code "16") (name "Net-(D3-CATHODE_(GREEN))") (class "Default")
      (node (ref "D3") (pin "2") (pinfunction "CATHODE_(GREEN)_2") (pintype "passive"))
      (node (ref "R9") (pin "1") (pinfunction "1_1") (pintype "passive"))
    )
    (net (code "17") (name "Net-(D3-CATHODE_(RED))") (class "Default")
      (node (ref "D3") (pin "1") (pinfunction "CATHODE_(RED)_1") (pintype "passive"))
      (node (ref "R8") (pin "2") (pinfunction "2_2") (pintype "passive"))
    )
    (net (code "18") (name "Net-(D4-CATHODE_(BLUE))") (class "Default")
      (node (ref "D4") (pin "3") (pinfunction "CATHODE_(BLUE)_3") (pintype "passive"))
      (node (ref "R10") (pin "1") (pinfunction "1_1") (pintype "passive"))
    )
    (net (code "19") (name "Net-(D4-CATHODE_(GREEN))") (class "Default")
      (node (ref "D4") (pin "2") (pinfunction "CATHODE_(GREEN)_2") (pintype "passive"))
      (node (ref "R14") (pin "1") (pinfunction "1_1") (pintype "passive"))
    )
    (net (code "20") (name "Net-(D4-CATHODE_(RED))") (class "Default")
      (node (ref "D4") (pin "1") (pinfunction "CATHODE_(RED)_1") (pintype "passive"))
      (node (ref "R13") (pin "2") (pinfunction "2_2") (pintype "passive"))
    )
    (net (code "21") (name "Net-(D5-CATHODE_(BLUE))") (class "Default")
      (node (ref "D5") (pin "3") (pinfunction "CATHODE_(BLUE)_3") (pintype "passive"))
      (node (ref "R11") (pin "1") (pinfunction "1_1") (pintype "passive"))
    )
    (net (code "22") (name "Net-(D5-CATHODE_(GREEN))") (class "Default")
      (node (ref "D5") (pin "2") (pinfunction "CATHODE_(GREEN)_2") (pintype "passive"))
      (node (ref "R16") (pin "1") (pinfunction "1_1") (pintype "passive"))
    )
    (net (code "23") (name "Net-(D5-CATHODE_(RED))") (class "Default")
      (node (ref "D5") (pin "1") (pinfunction "CATHODE_(RED)_1") (pintype "passive"))
      (node (ref "R15") (pin "2") (pinfunction "2_2") (pintype "passive"))
    )
    (net (code "24") (name "Net-(D6-CATHODE_(BLUE))") (class "Default")
      (node (ref "D6") (pin "3") (pinfunction "CATHODE_(BLUE)_3") (pintype "passive"))
      (node (ref "R12") (pin "1") (pinfunction "1_1") (pintype "passive"))
    )
    (net (code "25") (name "Net-(D6-CATHODE_(GREEN))") (class "Default")
      (node (ref "D6") (pin "2") (pinfunction "CATHODE_(GREEN)_2") (pintype "passive"))
      (node (ref "R18") (pin "1") (pinfunction "1_1") (pintype "passive"))
    )
    (net (code "26") (name "Net-(D6-CATHODE_(RED))") (class "Default")
      (node (ref "D6") (pin "1") (pinfunction "CATHODE_(RED)_1") (pintype "passive"))
      (node (ref "R17") (pin "2") (pinfunction "2_2") (pintype "passive"))
    )
    (net (code "27") (name "Net-(D7-CATHODE_(BLUE))") (class "Default")
      (node (ref "D7") (pin "3") (pinfunction "CATHODE_(BLUE)_3") (pintype "passive"))
      (node (ref "R20") (pin "2") (pinfunction "2_2") (pintype "passive"))
    )
    (net (code "28") (name "Net-(D7-CATHODE_(GREEN))") (class "Default")
      (node (ref "D7") (pin "2") (pinfunction "CATHODE_(GREEN)_2") (pintype "passive"))
      (node (ref "R24") (pin "1") (pinfunction "1_1") (pintype "passive"))
    )
    (net (code "29") (name "Net-(D7-CATHODE_(RED))") (class "Default")
      (node (ref "D7") (pin "1") (pinfunction "CATHODE_(RED)_1") (pintype "passive"))
      (node (ref "R23") (pin "1") (pinfunction "1_1") (pintype "passive"))
    )
    (net (code "30") (name "Net-(D8-CATHODE_(BLUE))") (class "Default")
      (node (ref "D8") (pin "3") (pinfunction "CATHODE_(BLUE)_3") (pintype "passive"))
      (node (ref "R21") (pin "2") (pinfunction "2_2") (pintype "passive"))
    )
    (net (code "31") (name "Net-(D8-CATHODE_(GREEN))") (class "Default")
      (node (ref "D8") (pin "2") (pinfunction "CATHODE_(GREEN)_2") (pintype "passive"))
      (node (ref "R26") (pin "1") (pinfunction "1_1") (pintype "passive"))
    )
    (net (code "32") (name "Net-(D8-CATHODE_(RED))") (class "Default")
      (node (ref "D8") (pin "1") (pinfunction "CATHODE_(RED)_1") (pintype "passive"))
      (node (ref "R25") (pin "2") (pinfunction "2_2") (pintype "passive"))
    )
    (net (code "33") (name "Net-(D9-CATHODE_(BLUE))") (class "Default")
      (node (ref "D9") (pin "3") (pinfunction "CATHODE_(BLUE)_3") (pintype "passive"))
      (node (ref "R22") (pin "2") (pinfunction "2_2") (pintype "passive"))
    )
    (net (code "34") (name "Net-(D9-CATHODE_(GREEN))") (class "Default")
      (node (ref "D9") (pin "2") (pinfunction "CATHODE_(GREEN)_2") (pintype "passive"))
      (node (ref "R28") (pin "1") (pinfunction "1_1") (pintype "passive"))
    )
    (net (code "35") (name "Net-(D9-CATHODE_(RED))") (class "Default")
      (node (ref "D9") (pin "1") (pinfunction "CATHODE_(RED)_1") (pintype "passive"))
      (node (ref "R27") (pin "2") (pinfunction "2_2") (pintype "passive"))
    )
    (net (code "36") (name "Net-(D10-CATHODE_(BLUE))") (class "Default")
      (node (ref "D10") (pin "3") (pinfunction "CATHODE_(BLUE)_3") (pintype "passive"))
      (node (ref "R30") (pin "1") (pinfunction "1_1") (pintype "passive"))
    )
    (net (code "37") (name "Net-(D10-CATHODE_(GREEN))") (class "Default")
      (node (ref "D10") (pin "2") (pinfunction "CATHODE_(GREEN)_2") (pintype "passive"))
      (node (ref "R34") (pin "1") (pinfunction "1_1") (pintype "passive"))
    )
    (net (code "38") (name "Net-(D10-CATHODE_(RED))") (class "Default")
      (node (ref "D10") (pin "1") (pinfunction "CATHODE_(RED)_1") (pintype "passive"))
      (node (ref "R33") (pin "2") (pinfunction "2_2") (pintype "passive"))
    )
    (net (code "39") (name "Net-(D11-CATHODE_(BLUE))") (class "Default")
      (node (ref "D11") (pin "3") (pinfunction "CATHODE_(BLUE)_3") (pintype "passive"))
      (node (ref "R31") (pin "1") (pinfunction "1_1") (pintype "passive"))
    )
    (net (code "40") (name "Net-(D11-CATHODE_(GREEN))") (class "Default")
      (node (ref "D11") (pin "2") (pinfunction "CATHODE_(GREEN)_2") (pintype "passive"))
      (node (ref "R36") (pin "1") (pinfunction "1_1") (pintype "passive"))
    )
    (net (code "41") (name "Net-(D11-CATHODE_(RED))") (class "Default")
      (node (ref "D11") (pin "1") (pinfunction "CATHODE_(RED)_1") (pintype "passive"))
      (node (ref "R35") (pin "2") (pinfunction "2_2") (pintype "passive"))
    )
    (net (code "42") (name "Net-(D12-CATHODE_(BLUE))") (class "Default")
      (node (ref "D12") (pin "3") (pinfunction "CATHODE_(BLUE)_3") (pintype "passive"))
      (node (ref "R32") (pin "1") (pinfunction "1_1") (pintype "passive"))
    )
    (net (code "43") (name "Net-(D12-CATHODE_(GREEN))") (class "Default")
      (node (ref "D12") (pin "2") (pinfunction "CATHODE_(GREEN)_2") (pintype "passive"))
      (node (ref "R38") (pin "1") (pinfunction "1_1") (pintype "passive"))
    )
    (net (code "44") (name "Net-(D12-CATHODE_(RED))") (class "Default")
      (node (ref "D12") (pin "1") (pinfunction "CATHODE_(RED)_1") (pintype "passive"))
      (node (ref "R37") (pin "2") (pinfunction "2_2") (pintype "passive"))
    )
    (net (code "45") (name "Net-(D13-CATHODE_(BLUE))") (class "Default")
      (node (ref "D13") (pin "3") (pinfunction "CATHODE_(BLUE)_3") (pintype "passive"))
      (node (ref "R39") (pin "2") (pinfunction "2_2") (pintype "passive"))
    )
    (net (code "46") (name "Net-(D13-CATHODE_(GREEN))") (class "Default")
      (node (ref "D13") (pin "2") (pinfunction "CATHODE_(GREEN)_2") (pintype "passive"))
      (node (ref "R43") (pin "1") (pinfunction "1_1") (pintype "passive"))
    )
    (net (code "47") (name "Net-(D13-CATHODE_(RED))") (class "Default")
      (node (ref "D13") (pin "1") (pinfunction "CATHODE_(RED)_1") (pintype "passive"))
      (node (ref "R42") (pin "2") (pinfunction "2_2") (pintype "passive"))
    )
    (net (code "48") (name "Net-(D14-CATHODE_(BLUE))") (class "Default")
      (node (ref "D14") (pin "3") (pinfunction "CATHODE_(BLUE)_3") (pintype "passive"))
      (node (ref "R40") (pin "1") (pinfunction "1_1") (pintype "passive"))
    )
    (net (code "49") (name "Net-(D14-CATHODE_(GREEN))") (class "Default")
      (node (ref "D14") (pin "2") (pinfunction "CATHODE_(GREEN)_2") (pintype "passive"))
      (node (ref "R45") (pin "1") (pinfunction "1_1") (pintype "passive"))
    )
    (net (code "50") (name "Net-(D14-CATHODE_(RED))") (class "Default")
      (node (ref "D14") (pin "1") (pinfunction "CATHODE_(RED)_1") (pintype "passive"))
      (node (ref "R44") (pin "2") (pinfunction "2_2") (pintype "passive"))
    )
    (net (code "51") (name "Net-(D15-CATHODE_(BLUE))") (class "Default")
      (node (ref "D15") (pin "3") (pinfunction "CATHODE_(BLUE)_3") (pintype "passive"))
      (node (ref "R46") (pin "1") (pinfunction "1_1") (pintype "passive"))
    )
    (net (code "52") (name "Net-(D15-CATHODE_(GREEN))") (class "Default")
      (node (ref "D15") (pin "2") (pinfunction "CATHODE_(GREEN)_2") (pintype "passive"))
      (node (ref "R49") (pin "1") (pinfunction "1_1") (pintype "passive"))
    )
    (net (code "53") (name "Net-(D15-CATHODE_(RED))") (class "Default")
      (node (ref "D15") (pin "1") (pinfunction "CATHODE_(RED)_1") (pintype "passive"))
      (node (ref "R48") (pin "2") (pinfunction "2_2") (pintype "passive"))
    )
    (net (code "54") (name "Net-(D16-CATHODE_(BLUE))") (class "Default")
      (node (ref "D16") (pin "3") (pinfunction "CATHODE_(BLUE)_3") (pintype "passive"))
      (node (ref "R47") (pin "1") (pinfunction "1_1") (pintype "passive"))
    )
    (net (code "55") (name "Net-(D16-CATHODE_(GREEN))") (class "Default")
      (node (ref "D16") (pin "2") (pinfunction "CATHODE_(GREEN)_2") (pintype "passive"))
      (node (ref "R51") (pin "1") (pinfunction "1_1") (pintype "passive"))
    )
    (net (code "56") (name "Net-(D16-CATHODE_(RED))") (class "Default")
      (node (ref "D16") (pin "1") (pinfunction "CATHODE_(RED)_1") (pintype "passive"))
      (node (ref "R50") (pin "2") (pinfunction "2_2") (pintype "passive"))
    )
    (net (code "57") (name "Net-(F1-Pad2)") (class "Default")
      (node (ref "F1") (pin "2") (pinfunction "2_2") (pintype "passive"))
      (node (ref "J1") (pin "1") (pinfunction "1_1") (pintype "passive"))
    )
  )
)
